# FPGA_Schematic.net
KiCad netlist of a schematic drawn in Altium Designer
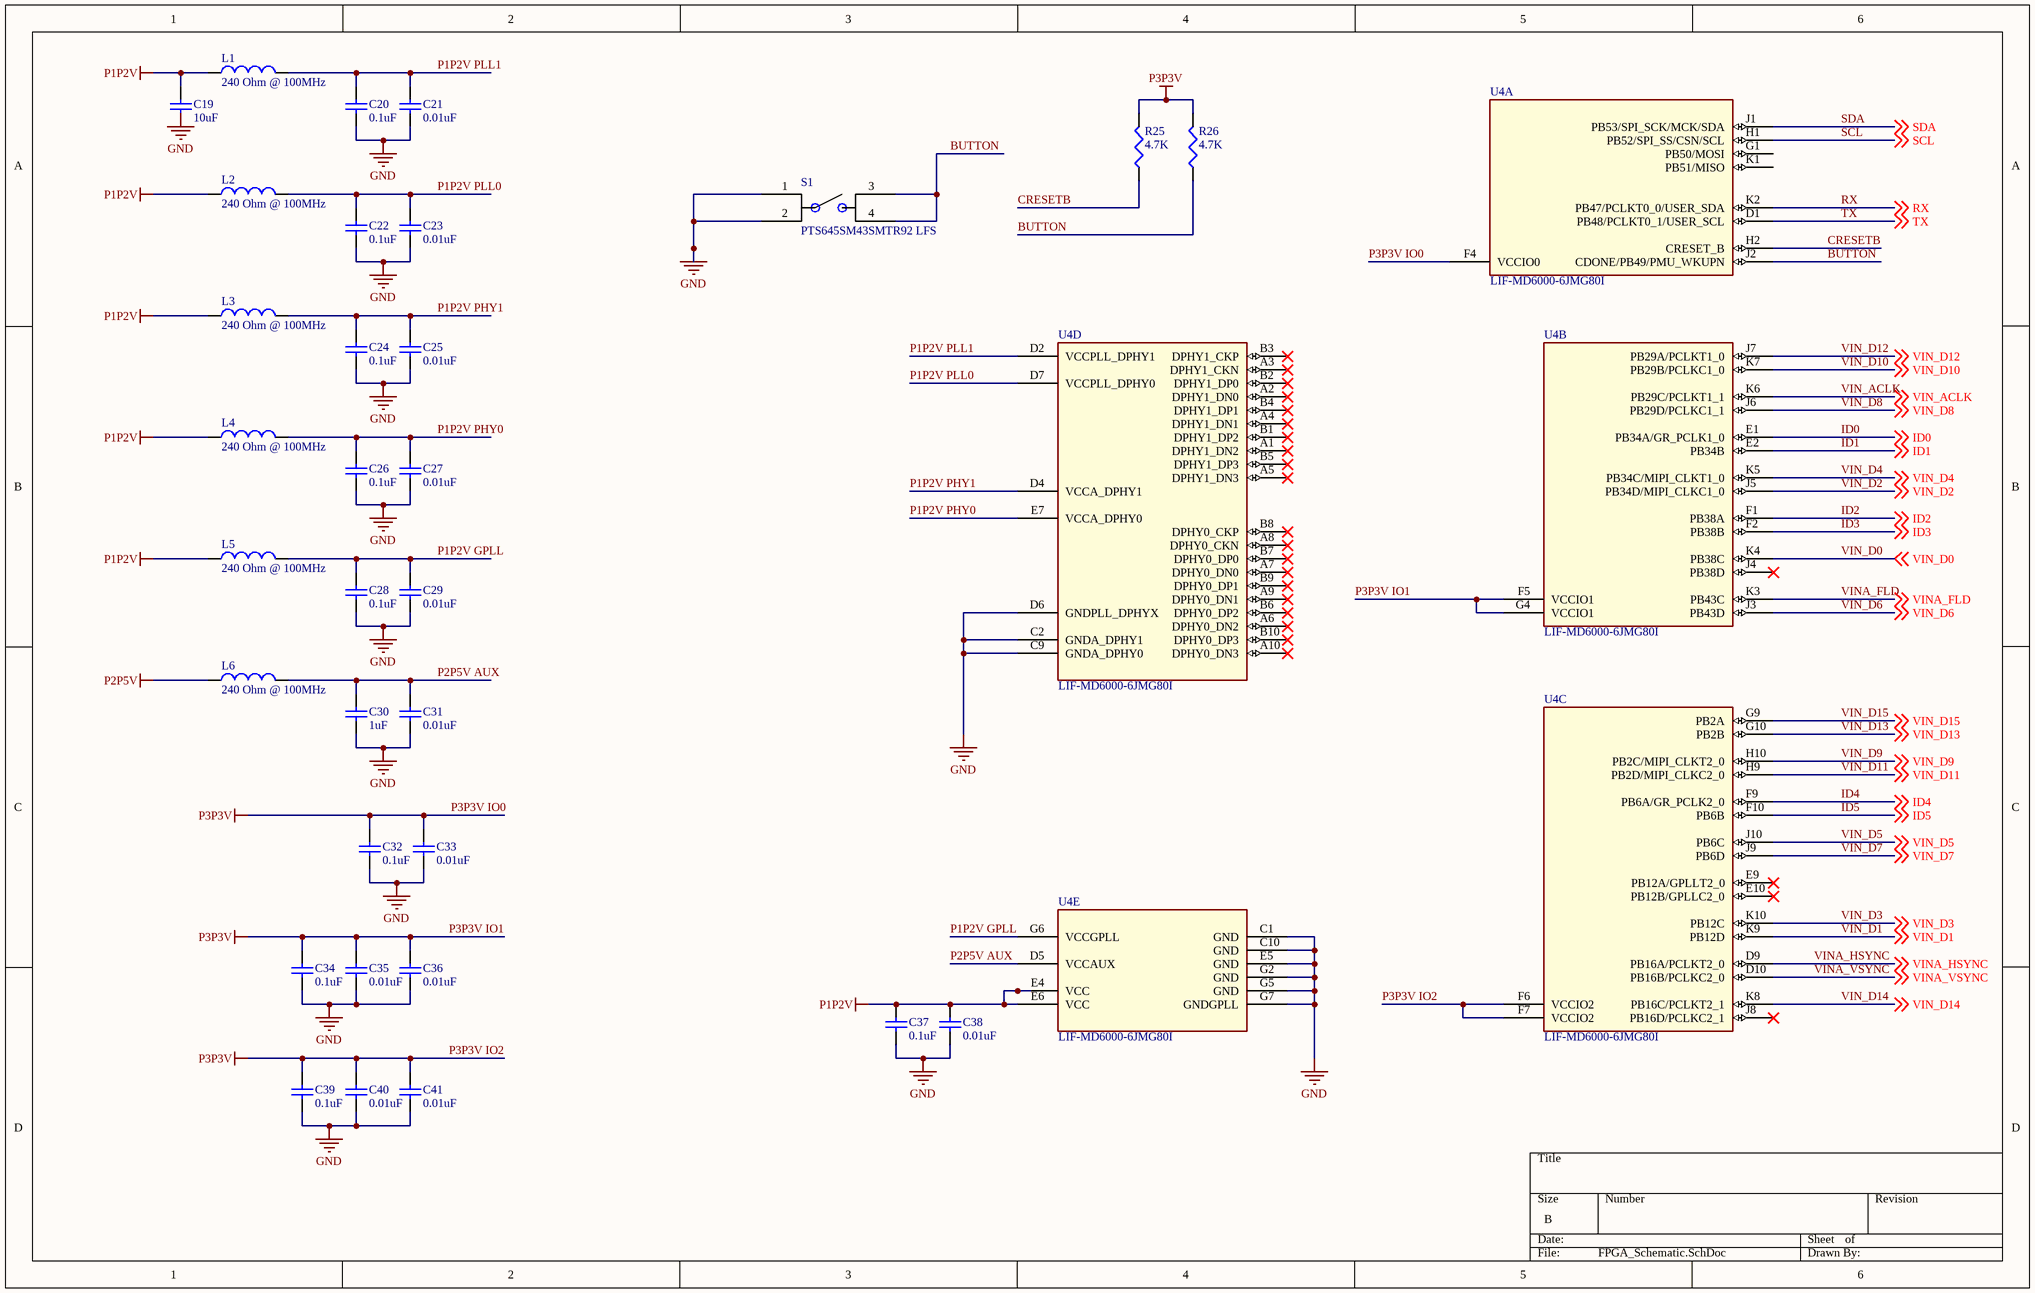
[diagram p0: FPGA_Schematic.SchDoc]

(export (version "E")
  (design (tool "Eeschema 10.0.6"))
  (components
    (comp (ref "C19")
      (value "10uF")
      (footprint "CAP_0402_MED")
      (description "CAP CER 10UF 6.3V X5R 0402")
      (fields (field (name "MFGPARTNO") "GRM155R60J106ME47D") (field (name "MFG") "Murata"))
      (libsource (lib "SLA3000-FPGA[4086]") (part "CMP-00647-A.1"))
    )
    (comp (ref "C20")
      (value "0.1uF")
      (footprint "CAP_0402_MED")
      (description "CAP CER 0.1UF 25V X7R 0402")
      (fields (field (name "SLA PART NO") "SL00150") (field (name "MFG") "TDK"))
      (libsource (lib "SLA3000-FPGA[4086]") (part "CMP-00496-A.6"))
    )
    (comp (ref "C21")
      (value "0.01uF")
      (footprint "CAP_0402_MED")
      (description "CAP CER 0.1UF 25V X7R 0402")
      (fields (field (name "SLA PART NO") "SL00150") (field (name "MFG") "TDK"))
      (libsource (lib "SLA3000-FPGA[4086]") (part "CMP-00496-A.6"))
    )
    (comp (ref "C22")
      (value "0.1uF")
      (footprint "CAP_0402_MED")
      (description "CAP CER 0.1UF 25V X7R 0402")
      (fields (field (name "SLA PART NO") "SL00150") (field (name "MFG") "TDK"))
      (libsource (lib "SLA3000-FPGA[4086]") (part "CMP-00496-A.6"))
    )
    (comp (ref "C23")
      (value "0.01uF")
      (footprint "CAP_0402_MED")
      (description "CAP CER 0.1UF 25V X7R 0402")
      (fields (field (name "SLA PART NO") "SL00150") (field (name "MFG") "TDK"))
      (libsource (lib "SLA3000-FPGA[4086]") (part "CMP-00496-A.6"))
    )
    (comp (ref "C24")
      (value "0.1uF")
      (footprint "CAP_0402_MED")
      (description "CAP CER 0.1UF 25V X7R 0402")
      (fields (field (name "SLA PART NO") "SL00150") (field (name "MFG") "TDK"))
      (libsource (lib "SLA3000-FPGA[4086]") (part "CMP-00496-A.6"))
    )
    (comp (ref "C25")
      (value "0.01uF")
      (footprint "CAP_0402_MED")
      (description "CAP CER 0.1UF 25V X7R 0402")
      (fields (field (name "SLA PART NO") "SL00150") (field (name "MFG") "TDK"))
      (libsource (lib "SLA3000-FPGA[4086]") (part "CMP-00496-A.6"))
    )
    (comp (ref "C26")
      (value "0.1uF")
      (footprint "CAP_0402_MED")
      (description "CAP CER 0.1UF 25V X7R 0402")
      (fields (field (name "SLA PART NO") "SL00150") (field (name "MFG") "TDK"))
      (libsource (lib "SLA3000-FPGA[4086]") (part "CMP-00496-A.6"))
    )
    (comp (ref "C27")
      (value "0.01uF")
      (footprint "CAP_0402_MED")
      (description "CAP CER 0.1UF 25V X7R 0402")
      (fields (field (name "SLA PART NO") "SL00150") (field (name "MFG") "TDK"))
      (libsource (lib "SLA3000-FPGA[4086]") (part "CMP-00496-A.6"))
    )
    (comp (ref "C28")
      (value "0.1uF")
      (footprint "CAP_0402_MED")
      (description "CAP CER 0.1UF 25V X7R 0402")
      (fields (field (name "SLA PART NO") "SL00150") (field (name "MFG") "TDK"))
      (libsource (lib "SLA3000-FPGA[4086]") (part "CMP-00496-A.6"))
    )
    (comp (ref "C29")
      (value "0.01uF")
      (footprint "CAP_0402_MED")
      (description "CAP CER 0.1UF 25V X7R 0402")
      (fields (field (name "SLA PART NO") "SL00150") (field (name "MFG") "TDK"))
      (libsource (lib "SLA3000-FPGA[4086]") (part "CMP-00496-A.6"))
    )
    (comp (ref "C30")
      (value "1uF")
      (footprint "CAP_0402_MED")
      (description "CAP CER 1UF 25V X5R 0402")
      (fields (field (name "MFGPARTNO") "EMK105BJ105KV-F") (field (name "MFG") "Taiyo Yuden"))
      (libsource (lib "SLA3000-FPGA[4086]") (part "CMP-00695-A.2"))
    )
    (comp (ref "C31")
      (value "0.01uF")
      (footprint "CAP_0402_MED")
      (description "CAP CER 0.1UF 25V X7R 0402")
      (fields (field (name "SLA PART NO") "SL00150") (field (name "MFG") "TDK"))
      (libsource (lib "SLA3000-FPGA[4086]") (part "CMP-00496-A.6"))
    )
    (comp (ref "C32")
      (value "0.1uF")
      (footprint "CAP_0402_MED")
      (description "CAP CER 0.1UF 25V X7R 0402")
      (fields (field (name "SLA PART NO") "SL00150") (field (name "MFG") "TDK"))
      (libsource (lib "SLA3000-FPGA[4086]") (part "CMP-00496-A.6"))
    )
    (comp (ref "C33")
      (value "0.01uF")
      (footprint "CAP_0402_MED")
      (description "CAP CER 0.1UF 25V X7R 0402")
      (fields (field (name "SLA PART NO") "SL00150") (field (name "MFG") "TDK"))
      (libsource (lib "SLA3000-FPGA[4086]") (part "CMP-00496-A.6"))
    )
    (comp (ref "C34")
      (value "0.1uF")
      (footprint "CAP_0402_MED")
      (description "CAP CER 0.1UF 25V X7R 0402")
      (fields (field (name "SLA PART NO") "SL00150") (field (name "MFG") "TDK"))
      (libsource (lib "SLA3000-FPGA[4086]") (part "CMP-00496-A.6"))
    )
    (comp (ref "C35")
      (value "0.01uF")
      (footprint "CAP_0402_MED")
      (description "CAP CER 0.1UF 25V X7R 0402")
      (fields (field (name "SLA PART NO") "SL00150") (field (name "MFG") "TDK"))
      (libsource (lib "SLA3000-FPGA[4086]") (part "CMP-00496-A.6"))
    )
    (comp (ref "C36")
      (value "0.01uF")
      (footprint "CAP_0402_MED")
      (description "CAP CER 0.1UF 25V X7R 0402")
      (fields (field (name "SLA PART NO") "SL00150") (field (name "MFG") "TDK"))
      (libsource (lib "SLA3000-FPGA[4086]") (part "CMP-00496-A.6"))
    )
    (comp (ref "C37")
      (value "0.1uF")
      (footprint "CAP_0402_MED")
      (description "CAP CER 0.1UF 25V X7R 0402")
      (fields (field (name "SLA PART NO") "SL00150") (field (name "MFG") "TDK"))
      (libsource (lib "SLA3000-FPGA[4086]") (part "CMP-00496-A.6"))
    )
    (comp (ref "C38")
      (value "0.01uF")
      (footprint "CAP_0402_MED")
      (description "CAP CER 0.1UF 25V X7R 0402")
      (fields (field (name "SLA PART NO") "SL00150") (field (name "MFG") "TDK"))
      (libsource (lib "SLA3000-FPGA[4086]") (part "CMP-00496-A.6"))
    )
    (comp (ref "C39")
      (value "0.1uF")
      (footprint "CAP_0402_MED")
      (description "CAP CER 0.1UF 25V X7R 0402")
      (fields (field (name "SLA PART NO") "SL00150") (field (name "MFG") "TDK"))
      (libsource (lib "SLA3000-FPGA[4086]") (part "CMP-00496-A.6"))
    )
    (comp (ref "C40")
      (value "0.01uF")
      (footprint "CAP_0402_MED")
      (description "CAP CER 0.1UF 25V X7R 0402")
      (fields (field (name "SLA PART NO") "SL00150") (field (name "MFG") "TDK"))
      (libsource (lib "SLA3000-FPGA[4086]") (part "CMP-00496-A.6"))
    )
    (comp (ref "C41")
      (value "0.01uF")
      (footprint "CAP_0402_MED")
      (description "CAP CER 0.1UF 25V X7R 0402")
      (fields (field (name "SLA PART NO") "SL00150") (field (name "MFG") "TDK"))
      (libsource (lib "SLA3000-FPGA[4086]") (part "CMP-00496-A.6"))
    )
    (comp (ref "L1")
      (value "240 Ohm @ 100MHz")
      (footprint "IND_0201_MED")
      (description "BLM03BD241SN1D FERRITE BEAD 240 OHM 0201 1LN")
      (fields (field (name "MFG") "Murata") (field (name "MFGPARTNO") "BLM03BD241SN1D"))
      (libsource (lib "SLA3000-FPGA[4086]") (part "CMP-00665-A.1"))
    )
    (comp (ref "L2")
      (value "240 Ohm @ 100MHz")
      (footprint "IND_0201_MED")
      (description "BLM03BD241SN1D FERRITE BEAD 240 OHM 0201 1LN")
      (fields (field (name "MFG") "Murata") (field (name "MFGPARTNO") "BLM03BD241SN1D"))
      (libsource (lib "SLA3000-FPGA[4086]") (part "CMP-00665-A.1"))
    )
    (comp (ref "L3")
      (value "240 Ohm @ 100MHz")
      (footprint "IND_0201_MED")
      (description "BLM03BD241SN1D FERRITE BEAD 240 OHM 0201 1LN")
      (fields (field (name "MFG") "Murata") (field (name "MFGPARTNO") "BLM03BD241SN1D"))
      (libsource (lib "SLA3000-FPGA[4086]") (part "CMP-00665-A.1"))
    )
    (comp (ref "L4")
      (value "240 Ohm @ 100MHz")
      (footprint "IND_0201_MED")
      (description "BLM03BD241SN1D FERRITE BEAD 240 OHM 0201 1LN")
      (fields (field (name "MFG") "Murata") (field (name "MFGPARTNO") "BLM03BD241SN1D"))
      (libsource (lib "SLA3000-FPGA[4086]") (part "CMP-00665-A.1"))
    )
    (comp (ref "L5")
      (value "240 Ohm @ 100MHz")
      (footprint "IND_0201_MED")
      (description "BLM03BD241SN1D FERRITE BEAD 240 OHM 0201 1LN")
      (fields (field (name "MFG") "Murata") (field (name "MFGPARTNO") "BLM03BD241SN1D"))
      (libsource (lib "SLA3000-FPGA[4086]") (part "CMP-00665-A.1"))
    )
    (comp (ref "L6")
      (value "240 Ohm @ 100MHz")
      (footprint "IND_0201_MED")
      (description "BLM03BD241SN1D FERRITE BEAD 240 OHM 0201 1LN")
      (fields (field (name "MFG") "Murata") (field (name "MFGPARTNO") "BLM03BD241SN1D"))
      (libsource (lib "SLA3000-FPGA[4086]") (part "CMP-00665-A.1"))
    )
    (comp (ref "R25")
      (value "4.7K")
      (footprint "RES_0402_MED")
      (description "RES SMD 4K7 OHM 1% 1/16W 0402")
      (fields (field (name "MFGPARTNO") "RC0402FR-074K7P") (field (name "MFG") "Yageo"))
      (libsource (lib "SLA3000-FPGA[4086]") (part "CMP-00761-A.1"))
    )
    (comp (ref "R26")
      (value "4.7K")
      (footprint "RES_0402_MED")
      (description "RES SMD 4K7 OHM 1% 1/16W 0402")
      (fields (field (name "MFGPARTNO") "RC0402FR-074K7P") (field (name "MFG") "Yageo"))
      (libsource (lib "SLA3000-FPGA[4086]") (part "CMP-00761-A.1"))
    )
    (comp (ref "S1")
      (value "PTS645SM43SMTR92 LFS")
      (footprint "PTS645SM43SMTR92 LFS")
      (description "PTS645SM43SMTR92 LFS SWITCH TACTILE SPST-NO 0.05A 12V")
      (fields (field (name "MFG") "C&K"))
      (libsource (lib "SLA3000-FPGA[4086]") (part "CMP-00660-2"))
    )
    (comp (ref "U4")
      (value "LIF-MD6000-6JMG80I")
      (footprint "CTFBGA-80")
      (description "LIF-MD6000-6JMG80I LATTICE CROSSLINK - INTERFACE MIPI D-")
      (fields (field (name "MFG") "Lattice"))
      (libsource (lib "SLA3000-FPGA[4086]") (part "CMP-00644-A.1"))
    )
  )
  (nets
    (net (code "1") (name "/BUTTON") (class "Default")
      (node (ref "R26") (pin "1") (pinfunction "1_1") (pintype "passive"))
      (node (ref "S1") (pin "3") (pinfunction "3_3") (pintype "passive"))
      (node (ref "S1") (pin "4") (pinfunction "4_4") (pintype "passive"))
      (node (ref "U4") (pin "J2") (pinfunction "CDONE/PB49/PMU_WKUPN_J2") (pintype "bidirectional"))
    )
    (net (code "2") (name "/CRESETB") (class "Default")
      (node (ref "R25") (pin "1") (pinfunction "1_1") (pintype "passive"))
      (node (ref "U4") (pin "H2") (pinfunction "CRESET_B_H2") (pintype "bidirectional"))
    )
    (net (code "3") (name "/P1P2V GPLL") (class "Default")
      (node (ref "C28") (pin "2") (pinfunction "2_2") (pintype "passive"))
      (node (ref "C29") (pin "2") (pinfunction "2_2") (pintype "passive"))
      (node (ref "L5") (pin "2") (pinfunction "2_2") (pintype "passive"))
      (node (ref "U4") (pin "G6") (pinfunction "VCCGPLL_G6") (pintype "power_in"))
    )
    (net (code "4") (name "/P1P2V PHY0") (class "Default")
      (node (ref "C26") (pin "2") (pinfunction "2_2") (pintype "passive"))
      (node (ref "C27") (pin "2") (pinfunction "2_2") (pintype "passive"))
      (node (ref "L4") (pin "2") (pinfunction "2_2") (pintype "passive"))
      (node (ref "U4") (pin "E7") (pinfunction "VCCA_DPHY0_E7") (pintype "power_in"))
    )
    (net (code "5") (name "/P1P2V PHY1") (class "Default")
      (node (ref "C24") (pin "2") (pinfunction "2_2") (pintype "passive"))
      (node (ref "C25") (pin "2") (pinfunction "2_2") (pintype "passive"))
      (node (ref "L3") (pin "2") (pinfunction "2_2") (pintype "passive"))
      (node (ref "U4") (pin "D4") (pinfunction "VCCA_DPHY1_D4") (pintype "power_in"))
    )
    (net (code "6") (name "/P1P2V PLL0") (class "Default")
      (node (ref "C22") (pin "2") (pinfunction "2_2") (pintype "passive"))
      (node (ref "C23") (pin "2") (pinfunction "2_2") (pintype "passive"))
      (node (ref "L2") (pin "2") (pinfunction "2_2") (pintype "passive"))
      (node (ref "U4") (pin "D7") (pinfunction "VCCPLL_DPHY0_D7") (pintype "power_in"))
    )
    (net (code "7") (name "/P1P2V PLL1") (class "Default")
      (node (ref "C20") (pin "2") (pinfunction "2_2") (pintype "passive"))
      (node (ref "C21") (pin "2") (pinfunction "2_2") (pintype "passive"))
      (node (ref "L1") (pin "2") (pinfunction "2_2") (pintype "passive"))
      (node (ref "U4") (pin "D2") (pinfunction "VCCPLL_DPHY1_D2") (pintype "power_in"))
    )
    (net (code "8") (name "/P2P5V AUX") (class "Default")
      (node (ref "C30") (pin "2") (pinfunction "2_2") (pintype "passive"))
      (node (ref "C31") (pin "2") (pinfunction "2_2") (pintype "passive"))
      (node (ref "L6") (pin "2") (pinfunction "2_2") (pintype "passive"))
      (node (ref "U4") (pin "D5") (pinfunction "VCCAUX_D5") (pintype "power_in"))
    )
    (net (code "9") (name "GND") (class "Default")
      (node (ref "C20") (pin "1") (pinfunction "1_1") (pintype "passive"))
      (node (ref "C21") (pin "1") (pinfunction "1_1") (pintype "passive"))
      (node (ref "C22") (pin "1") (pinfunction "1_1") (pintype "passive"))
      (node (ref "C23") (pin "1") (pinfunction "1_1") (pintype "passive"))
      (node (ref "C24") (pin "1") (pinfunction "1_1") (pintype "passive"))
      (node (ref "C25") (pin "1") (pinfunction "1_1") (pintype "passive"))
      (node (ref "C26") (pin "1") (pinfunction "1_1") (pintype "passive"))
      (node (ref "C27") (pin "1") (pinfunction "1_1") (pintype "passive"))
      (node (ref "C28") (pin "1") (pinfunction "1_1") (pintype "passive"))
      (node (ref "C29") (pin "1") (pinfunction "1_1") (pintype "passive"))
      (node (ref "C30") (pin "1") (pinfunction "1_1") (pintype "passive"))
      (node (ref "C31") (pin "1") (pinfunction "1_1") (pintype "passive"))
      (node (ref "C32") (pin "1") (pinfunction "1_1") (pintype "passive"))
      (node (ref "C33") (pin "1") (pinfunction "1_1") (pintype "passive"))
      (node (ref "C34") (pin "1") (pinfunction "1_1") (pintype "passive"))
      (node (ref "C35") (pin "1") (pinfunction "1_1") (pintype "passive"))
      (node (ref "C36") (pin "1") (pinfunction "1_1") (pintype "passive"))
      (node (ref "C37") (pin "1") (pinfunction "1_1") (pintype "passive"))
      (node (ref "C38") (pin "1") (pinfunction "1_1") (pintype "passive"))
      (node (ref "C39") (pin "1") (pinfunction "1_1") (pintype "passive"))
      (node (ref "C40") (pin "1") (pinfunction "1_1") (pintype "passive"))
      (node (ref "C41") (pin "1") (pinfunction "1_1") (pintype "passive"))
      (node (ref "S1") (pin "1") (pinfunction "1_1") (pintype "passive"))
      (node (ref "S1") (pin "2") (pinfunction "2_2") (pintype "passive"))
      (node (ref "U4") (pin "C1") (pinfunction "GND_C1") (pintype "power_in"))
      (node (ref "U4") (pin "C10") (pinfunction "GND_C10") (pintype "power_in"))
      (node (ref "U4") (pin "C2") (pinfunction "GNDA_DPHY1_C2") (pintype "power_in"))
      (node (ref "U4") (pin "C9") (pinfunction "GNDA_DPHY0_C9") (pintype "power_in"))
      (node (ref "U4") (pin "D6") (pinfunction "GNDPLL_DPHYX_D6") (pintype "power_in"))
      (node (ref "U4") (pin "E5") (pinfunction "GND_E5") (pintype "power_in"))
      (node (ref "U4") (pin "G2") (pinfunction "GND_G2") (pintype "power_in"))
      (node (ref "U4") (pin "G5") (pinfunction "GND_G5") (pintype "power_in"))
      (node (ref "U4") (pin "G7") (pinfunction "GNDGPLL_G7") (pintype "power_in"))
    )
    (net (code "10") (name "ID0") (class "Default")
      (node (ref "U4") (pin "E1") (pinfunction "PB34A/GR_PCLK1_0_E1") (pintype "bidirectional"))
    )
    (net (code "11") (name "ID1") (class "Default")
      (node (ref "U4") (pin "E2") (pinfunction "PB34B_E2") (pintype "bidirectional"))
    )
    (net (code "12") (name "ID2") (class "Default")
      (node (ref "U4") (pin "F1") (pinfunction "PB38A_F1") (pintype "bidirectional"))
    )
    (net (code "13") (name "ID3") (class "Default")
      (node (ref "U4") (pin "F2") (pinfunction "PB38B_F2") (pintype "bidirectional"))
    )
    (net (code "14") (name "ID4") (class "Default")
      (node (ref "U4") (pin "F9") (pinfunction "PB6A/GR_PCLK2_0_F9") (pintype "bidirectional"))
    )
    (net (code "15") (name "ID5") (class "Default")
      (node (ref "U4") (pin "F10") (pinfunction "PB6B_F10") (pintype "bidirectional"))
    )
    (net (code "16") (name "P1P2V") (class "Default")
      (node (ref "C19") (pin "2") (pinfunction "2_2") (pintype "passive"))
      (node (ref "C37") (pin "2") (pinfunction "2_2") (pintype "passive"))
      (node (ref "C38") (pin "2") (pinfunction "2_2") (pintype "passive"))
      (node (ref "L1") (pin "1") (pinfunction "1_1") (pintype "passive"))
      (node (ref "L2") (pin "1") (pinfunction "1_1") (pintype "passive"))
      (node (ref "L3") (pin "1") (pinfunction "1_1") (pintype "passive"))
      (node (ref "L4") (pin "1") (pinfunction "1_1") (pintype "passive"))
      (node (ref "L5") (pin "1") (pinfunction "1_1") (pintype "passive"))
      (node (ref "U4") (pin "E4") (pinfunction "VCC_E4") (pintype "power_in"))
      (node (ref "U4") (pin "E6") (pinfunction "VCC_E6") (pintype "power_in"))
    )
    (net (code "17") (name "P2P5V") (class "Default")
      (node (ref "L6") (pin "1") (pinfunction "1_1") (pintype "passive"))
    )
    (net (code "18") (name "P3P3V") (class "Default")
      (node (ref "C32") (pin "2") (pinfunction "2_2") (pintype "passive"))
      (node (ref "C33") (pin "2") (pinfunction "2_2") (pintype "passive"))
      (node (ref "C34") (pin "2") (pinfunction "2_2") (pintype "passive"))
      (node (ref "C35") (pin "2") (pinfunction "2_2") (pintype "passive"))
      (node (ref "C36") (pin "2") (pinfunction "2_2") (pintype "passive"))
      (node (ref "C39") (pin "2") (pinfunction "2_2") (pintype "passive"))
      (node (ref "C40") (pin "2") (pinfunction "2_2") (pintype "passive"))
      (node (ref "C41") (pin "2") (pinfunction "2_2") (pintype "passive"))
      (node (ref "R25") (pin "2") (pinfunction "2_2") (pintype "passive"))
      (node (ref "R26") (pin "2") (pinfunction "2_2") (pintype "passive"))
      (node (ref "U4") (pin "F4") (pinfunction "VCCIO0_F4") (pintype "power_in"))
      (node (ref "U4") (pin "F5") (pinfunction "VCCIO1_F5") (pintype "power_in"))
      (node (ref "U4") (pin "F6") (pinfunction "VCCIO2_F6") (pintype "power_in"))
      (node (ref "U4") (pin "F7") (pinfunction "VCCIO2_F7") (pintype "power_in"))
      (node (ref "U4") (pin "G4") (pinfunction "VCCIO1_G4") (pintype "power_in"))
    )
    (net (code "19") (name "RX") (class "Default")
      (node (ref "U4") (pin "K2") (pinfunction "PB47/PCLKT0_0/USER_SDA_K2") (pintype "bidirectional"))
    )
    (net (code "20") (name "SCL") (class "Default")
      (node (ref "U4") (pin "H1") (pinfunction "PB52/SPI_SS/CSN/SCL_H1") (pintype "bidirectional"))
    )
    (net (code "21") (name "SDA") (class "Default")
      (node (ref "U4") (pin "J1") (pinfunction "PB53/SPI_SCK/MCK/SDA_J1") (pintype "bidirectional"))
    )
    (net (code "22") (name "TX") (class "Default")
      (node (ref "U4") (pin "D1") (pinfunction "PB48/PCLKT0_1/USER_SCL_D1") (pintype "bidirectional"))
    )
    (net (code "23") (name "VINA_FLD") (class "Default")
      (node (ref "U4") (pin "K3") (pinfunction "PB43C_K3") (pintype "bidirectional"))
    )
    (net (code "24") (name "VINA_HSYNC") (class "Default")
      (node (ref "U4") (pin "D9") (pinfunction "PB16A/PCLKT2_0_D9") (pintype "bidirectional"))
    )
    (net (code "25") (name "VINA_VSYNC") (class "Default")
      (node (ref "U4") (pin "D10") (pinfunction "PB16B/PCLKC2_0_D10") (pintype "bidirectional"))
    )
    (net (code "26") (name "VIN_ACLK") (class "Default")
      (node (ref "U4") (pin "K6") (pinfunction "PB29C/PCLKT1_1_K6") (pintype "bidirectional"))
    )
    (net (code "27") (name "VIN_D0") (class "Default")
      (node (ref "U4") (pin "K4") (pinfunction "PB38C_K4") (pintype "bidirectional"))
    )
    (net (code "28") (name "VIN_D1") (class "Default")
      (node (ref "U4") (pin "K9") (pinfunction "PB12D_K9") (pintype "bidirectional"))
    )
    (net (code "29") (name "VIN_D2") (class "Default")
      (node (ref "U4") (pin "J5") (pinfunction "PB34D/MIPI_CLKC1_0_J5") (pintype "bidirectional"))
    )
    (net (code "30") (name "VIN_D3") (class "Default")
      (node (ref "U4") (pin "K10") (pinfunction "PB12C_K10") (pintype "bidirectional"))
    )
    (net (code "31") (name "VIN_D4") (class "Default")
      (node (ref "U4") (pin "K5") (pinfunction "PB34C/MIPI_CLKT1_0_K5") (pintype "bidirectional"))
    )
    (net (code "32") (name "VIN_D5") (class "Default")
      (node (ref "U4") (pin "J10") (pinfunction "PB6C_J10") (pintype "bidirectional"))
    )
    (net (code "33") (name "VIN_D6") (class "Default")
      (node (ref "U4") (pin "J3") (pinfunction "PB43D_J3") (pintype "bidirectional"))
    )
    (net (code "34") (name "VIN_D7") (class "Default")
      (node (ref "U4") (pin "J9") (pinfunction "PB6D_J9") (pintype "bidirectional"))
    )
    (net (code "35") (name "VIN_D8") (class "Default")
      (node (ref "U4") (pin "J6") (pinfunction "PB29D/PCLKC1_1_J6") (pintype "bidirectional"))
    )
    (net (code "36") (name "VIN_D9") (class "Default")
      (node (ref "U4") (pin "H10") (pinfunction "PB2C/MIPI_CLKT2_0_H10") (pintype "bidirectional"))
    )
    (net (code "37") (name "VIN_D10") (class "Default")
      (node (ref "U4") (pin "K7") (pinfunction "PB29B/PCLKC1_0_K7") (pintype "bidirectional"))
    )
    (net (code "38") (name "VIN_D11") (class "Default")
      (node (ref "U4") (pin "H9") (pinfunction "PB2D/MIPI_CLKC2_0_H9") (pintype "bidirectional"))
    )
    (net (code "39") (name "VIN_D12") (class "Default")
      (node (ref "U4") (pin "J7") (pinfunction "PB29A/PCLKT1_0_J7") (pintype "bidirectional"))
    )
    (net (code "40") (name "VIN_D13") (class "Default")
      (node (ref "U4") (pin "G10") (pinfunction "PB2B_G10") (pintype "bidirectional"))
    )
    (net (code "41") (name "VIN_D14") (class "Default")
      (node (ref "U4") (pin "K8") (pinfunction "PB16C/PCLKT2_1_K8") (pintype "bidirectional"))
    )
    (net (code "42") (name "VIN_D15") (class "Default")
      (node (ref "U4") (pin "G9") (pinfunction "PB2A_G9") (pintype "bidirectional"))
    )
    (net (code "43") (name "unconnected-(C19-Pad1)") (class "Default")
      (node (ref "C19") (pin "1") (pinfunction "1_1") (pintype "passive"))
    )
    (net (code "44") (name "unconnected-(U4A-PB50{slash}MOSI-PadG1)") (class "Default")
      (node (ref "U4") (pin "G1") (pinfunction "PB50/MOSI_G1") (pintype "bidirectional"))
    )
    (net (code "45") (name "unconnected-(U4A-PB51{slash}MISO-PadK1)") (class "Default")
      (node (ref "U4") (pin "K1") (pinfunction "PB51/MISO_K1") (pintype "bidirectional"))
    )
    (net (code "46") (name "unconnected-(U4B-PB38D-PadJ4)") (class "Default")
      (node (ref "U4") (pin "J4") (pinfunction "PB38D_J4") (pintype "bidirectional+no_connect"))
    )
    (net (code "47") (name "unconnected-(U4C-PB12A{slash}GPLLT2_0-PadE9)") (class "Default")
      (node (ref "U4") (pin "E9") (pinfunction "PB12A/GPLLT2_0_E9") (pintype "bidirectional+no_connect"))
    )
    (net (code "48") (name "unconnected-(U4C-PB12B{slash}GPLLC2_0-PadE10)") (class "Default")
      (node (ref "U4") (pin "E10") (pinfunction "PB12B/GPLLC2_0_E10") (pintype "bidirectional+no_connect"))
    )
    (net (code "49") (name "unconnected-(U4C-PB16D{slash}PCLKC2_1-PadJ8)") (class "Default")
      (node (ref "U4") (pin "J8") (pinfunction "PB16D/PCLKC2_1_J8") (pintype "bidirectional+no_connect"))
    )
    (net (code "50") (name "unconnected-(U4D-DPHY0_CKN-PadA8)") (class "Default")
      (node (ref "U4") (pin "A8") (pinfunction "DPHY0_CKN_A8") (pintype "bidirectional+no_connect"))
    )
    (net (code "51") (name "unconnected-(U4D-DPHY0_CKP-PadB8)") (class "Default")
      (node (ref "U4") (pin "B8") (pinfunction "DPHY0_CKP_B8") (pintype "bidirectional+no_connect"))
    )
    (net (code "52") (name "unconnected-(U4D-DPHY0_DN0-PadA7)") (class "Default")
      (node (ref "U4") (pin "A7") (pinfunction "DPHY0_DN0_A7") (pintype "bidirectional+no_connect"))
    )
    (net (code "53") (name "unconnected-(U4D-DPHY0_DN1-PadA9)") (class "Default")
      (node (ref "U4") (pin "A9") (pinfunction "DPHY0_DN1_A9") (pintype "bidirectional+no_connect"))
    )
    (net (code "54") (name "unconnected-(U4D-DPHY0_DN2-PadA6)") (class "Default")
      (node (ref "U4") (pin "A6") (pinfunction "DPHY0_DN2_A6") (pintype "bidirectional+no_connect"))
    )
    (net (code "55") (name "unconnected-(U4D-DPHY0_DN3-PadA10)") (class "Default")
      (node (ref "U4") (pin "A10") (pinfunction "DPHY0_DN3_A10") (pintype "bidirectional+no_connect"))
    )
    (net (code "56") (name "unconnected-(U4D-DPHY0_DP0-PadB7)") (class "Default")
      (node (ref "U4") (pin "B7") (pinfunction "DPHY0_DP0_B7") (pintype "bidirectional+no_connect"))
    )
    (net (code "57") (name "unconnected-(U4D-DPHY0_DP1-PadB9)") (class "Default")
      (node (ref "U4") (pin "B9") (pinfunction "DPHY0_DP1_B9") (pintype "bidirectional+no_connect"))
    )
    (net (code "58") (name "unconnected-(U4D-DPHY0_DP2-PadB6)") (class "Default")
      (node (ref "U4") (pin "B6") (pinfunction "DPHY0_DP2_B6") (pintype "bidirectional+no_connect"))
    )
    (net (code "59") (name "unconnected-(U4D-DPHY0_DP3-PadB10)") (class "Default")
      (node (ref "U4") (pin "B10") (pinfunction "DPHY0_DP3_B10") (pintype "bidirectional+no_connect"))
    )
    (net (code "60") (name "unconnected-(U4D-DPHY1_CKN-PadA3)") (class "Default")
      (node (ref "U4") (pin "A3") (pinfunction "DPHY1_CKN_A3") (pintype "bidirectional+no_connect"))
    )
    (net (code "61") (name "unconnected-(U4D-DPHY1_CKP-PadB3)") (class "Default")
      (node (ref "U4") (pin "B3") (pinfunction "DPHY1_CKP_B3") (pintype "bidirectional+no_connect"))
    )
    (net (code "62") (name "unconnected-(U4D-DPHY1_DN0-PadA2)") (class "Default")
      (node (ref "U4") (pin "A2") (pinfunction "DPHY1_DN0_A2") (pintype "bidirectional+no_connect"))
    )
    (net (code "63") (name "unconnected-(U4D-DPHY1_DN1-PadA4)") (class "Default")
      (node (ref "U4") (pin "A4") (pinfunction "DPHY1_DN1_A4") (pintype "bidirectional+no_connect"))
    )
    (net (code "64") (name "unconnected-(U4D-DPHY1_DN2-PadA1)") (class "Default")
      (node (ref "U4") (pin "A1") (pinfunction "DPHY1_DN2_A1") (pintype "bidirectional+no_connect"))
    )
    (net (code "65") (name "unconnected-(U4D-DPHY1_DN3-PadA5)") (class "Default")
      (node (ref "U4") (pin "A5") (pinfunction "DPHY1_DN3_A5") (pintype "bidirectional+no_connect"))
    )
    (net (code "66") (name "unconnected-(U4D-DPHY1_DP0-PadB2)") (class "Default")
      (node (ref "U4") (pin "B2") (pinfunction "DPHY1_DP0_B2") (pintype "bidirectional+no_connect"))
    )
    (net (code "67") (name "unconnected-(U4D-DPHY1_DP1-PadB4)") (class "Default")
      (node (ref "U4") (pin "B4") (pinfunction "DPHY1_DP1_B4") (pintype "bidirectional+no_connect"))
    )
    (net (code "68") (name "unconnected-(U4D-DPHY1_DP2-PadB1)") (class "Default")
      (node (ref "U4") (pin "B1") (pinfunction "DPHY1_DP2_B1") (pintype "bidirectional+no_connect"))
    )
    (net (code "69") (name "unconnected-(U4D-DPHY1_DP3-PadB5)") (class "Default")
      (node (ref "U4") (pin "B5") (pinfunction "DPHY1_DP3_B5") (pintype "bidirectional+no_connect"))
    )
  )
)
